# Power_Management_2FMC_RTM.net
KiCad netlist of a schematic drawn in Altium Designer
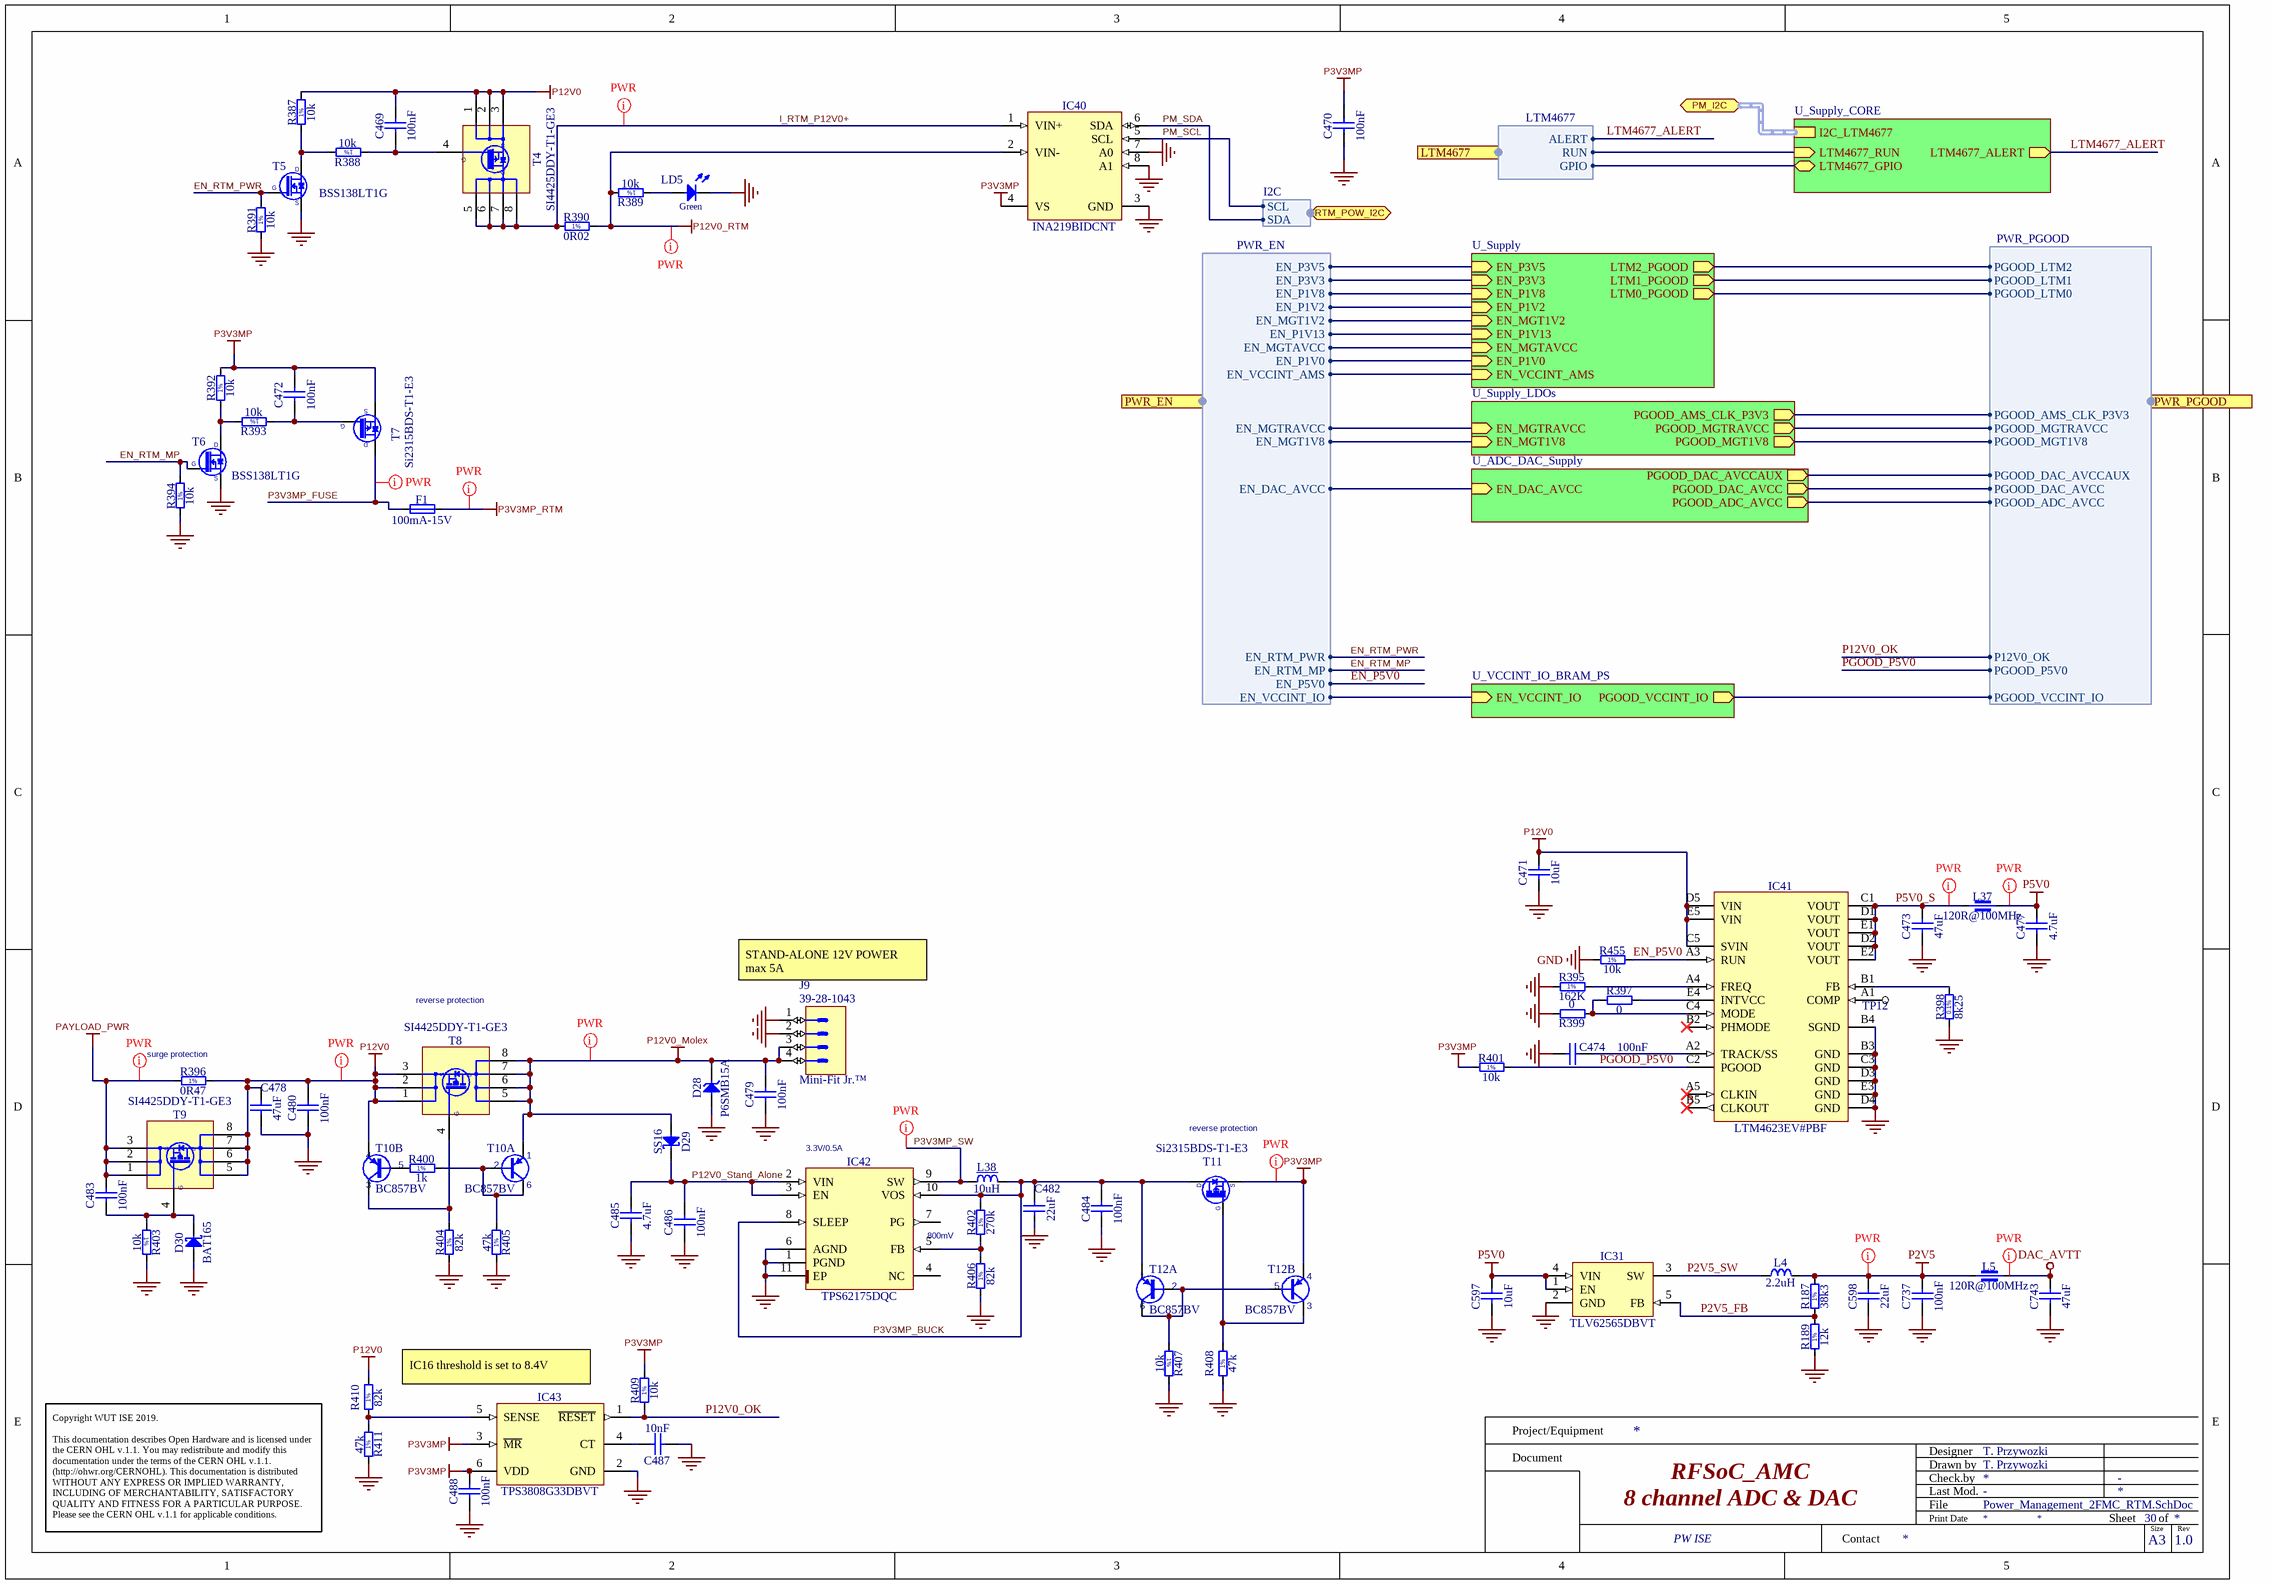
[diagram p0: Power_Management_2FMC_RTM.SchDoc]

(export (version "E")
  (design (tool "Eeschema 10.0.6"))
  (components
    (comp (ref "C469")
      (value "100nF")
      (footprint "CAPC1005X55N")
      (description "Non-polarised capacitor")
      (fields
        (field (name "MANUFACTURER PART NUMBER") "CC0402_100NF_16V_10%_X5R")
        (field (name "MANUFACTURER") "GENERIC")
        (field (name "AUTHOR") "CERN DEM JLC")
      )
      (libsource (lib "Capacitors") (part "Capacitor - non polarized"))
    )
    (comp (ref "C470")
      (value "100nF")
      (footprint "CAPC1005X55N")
      (description "Non-polarised capacitor")
      (fields
        (field (name "MANUFACTURER PART NUMBER") "CC0402_100NF_16V_10%_X5R")
        (field (name "MANUFACTURER") "GENERIC")
        (field (name "AUTHOR") "CERN DEM JLC")
      )
      (libsource (lib "Capacitors") (part "Capacitor - non polarized"))
    )
    (comp (ref "C471")
      (value "10uF")
      (footprint "CAPC2012X95N")
      (description "Non-polarised capacitor")
      (fields
        (field (name "PART NUMBER") "CC0805_10UF_25V_10%_X5R")
        (field (name "VOLTAGE") "25V")
        (field (name "AUTHOR") "CERN DEM JLC")
      )
      (libsource (lib "Capacitors") (part "Capacitor - non polarized"))
    )
    (comp (ref "C472")
      (value "100nF")
      (footprint "CAPC1005X55N")
      (description "Non-polarised capacitor")
      (fields
        (field (name "MANUFACTURER PART NUMBER") "CC0402_100NF_16V_10%_X5R")
        (field (name "MANUFACTURER") "GENERIC")
        (field (name "AUTHOR") "CERN DEM JLC")
      )
      (libsource (lib "Capacitors") (part "Capacitor - non polarized"))
    )
    (comp (ref "C473")
      (value "47uF")
      (footprint "CAPC2012X140N")
      (description "Non-polarised capacitor")
      (fields
        (field (name "MANUFACTURER PART NUMBER") "CC0805_47UF_6.3V_20%_X5R")
        (field (name "MANUFACTURER") "GENERIC")
        (field (name "AUTHOR") "CERN DEM JLC")
      )
      (libsource (lib "Capacitors") (part "Capacitor - non polarized"))
    )
    (comp (ref "C474")
      (value "100nF")
      (footprint "CAPC1005X55N")
      (description "Non-polarised capacitor")
      (fields
        (field (name "PART NUMBER") "CC0402_100NF_16V_10%_X5R")
        (field (name "VOLTAGE") "16V")
        (field (name "AUTHOR") "CERN DEM JLC")
      )
      (libsource (lib "Capacitors") (part "Capacitor - non polarized"))
    )
    (comp (ref "C477")
      (value "4.7uF")
      (footprint "CAPC1709X95N")
      (description "Non-polarised capacitor")
      (fields
        (field (name "MANUFACTURER PART NUMBER") "CC0603_4.7UF_16V_10%_X5R")
        (field (name "MANUFACTURER") "GENERIC")
        (field (name "AUTHOR") "CERN DEM JLC")
      )
      (libsource (lib "Capacitors") (part "Capacitor - non polarized"))
    )
    (comp (ref "C478")
      (value "47uF")
      (footprint "CAPC3216X180N")
      (description "Non-polarised capacitor")
      (fields
        (field (name "MANUFACTURER PART NUMBER") "CC1206_47UF_25V_20%_X5R")
        (field (name "MANUFACTURER") "GENERIC")
        (field (name "AUTHOR") "CERN DEM JLC")
      )
      (libsource (lib "Capacitors") (part "Capacitor - non polarized"))
    )
    (comp (ref "C479")
      (value "100nF")
      (footprint "CAPC1005X55N")
      (description "Non-polarised capacitor")
      (fields
        (field (name "MANUFACTURER PART NUMBER") "CC0402_100NF_16V_10%_X5R")
        (field (name "MANUFACTURER") "GENERIC")
        (field (name "AUTHOR") "CERN DEM JLC")
      )
      (libsource (lib "Capacitors") (part "Capacitor - non polarized"))
    )
    (comp (ref "C480")
      (value "100nF")
      (footprint "CAPC1005X55N")
      (description "Non-polarised capacitor")
      (fields
        (field (name "MANUFACTURER PART NUMBER") "CC0402_100NF_16V_10%_X5R")
        (field (name "MANUFACTURER") "GENERIC")
        (field (name "AUTHOR") "CERN DEM JLC")
      )
      (libsource (lib "Capacitors") (part "Capacitor - non polarized"))
    )
    (comp (ref "C482")
      (value "22uF")
      (footprint "CAPC2012X135N")
      (description "Non-polarised capacitor")
      (fields
        (field (name "MANUFACTURER PART NUMBER") "CC0805_22UF_16V_10%_X5R")
        (field (name "MANUFACTURER") "GENERIC")
        (field (name "AUTHOR") "CERN DEM JLC")
      )
      (libsource (lib "Capacitors") (part "Capacitor - non polarized"))
    )
    (comp (ref "C483")
      (value "100nF")
      (footprint "CAPC1005X55N")
      (description "Non-polarised capacitor")
      (fields
        (field (name "MANUFACTURER PART NUMBER") "CC0402_100NF_16V_10%_X5R")
        (field (name "MANUFACTURER") "GENERIC")
        (field (name "AUTHOR") "CERN DEM JLC")
      )
      (libsource (lib "Capacitors") (part "Capacitor - non polarized"))
    )
    (comp (ref "C484")
      (value "100nF")
      (footprint "CAPC1005X55N")
      (description "Non-polarised capacitor")
      (fields
        (field (name "MANUFACTURER PART NUMBER") "CC0402_100NF_16V_10%_X5R")
        (field (name "MANUFACTURER") "GENERIC")
        (field (name "AUTHOR") "CERN DEM JLC")
      )
      (libsource (lib "Capacitors") (part "Capacitor - non polarized"))
    )
    (comp (ref "C485")
      (value "4.7uF")
      (footprint "CAPC1709X95N")
      (description "Non-polarised capacitor")
      (fields
        (field (name "MANUFACTURER PART NUMBER") "CC0603_4.7UF_16V_10%_X5R")
        (field (name "MANUFACTURER") "GENERIC")
        (field (name "AUTHOR") "CERN DEM JLC")
      )
      (libsource (lib "Capacitors") (part "Capacitor - non polarized"))
    )
    (comp (ref "C486")
      (value "100nF")
      (footprint "CAPC1005X55N")
      (description "Non-polarised capacitor")
      (fields
        (field (name "MANUFACTURER PART NUMBER") "CC0402_100NF_16V_10%_X5R")
        (field (name "MANUFACTURER") "GENERIC")
        (field (name "AUTHOR") "CERN DEM JLC")
      )
      (libsource (lib "Capacitors") (part "Capacitor - non polarized"))
    )
    (comp (ref "C487")
      (value "10nF")
      (footprint "CAPC1005X55N")
      (description "Non-polarised capacitor")
      (fields
        (field (name "MANUFACTURER PART NUMBER") "CC0402_10NF_16V_10%_X7R")
        (field (name "MANUFACTURER") "GENERIC")
        (field (name "AUTHOR") "CERN DEM JLC")
      )
      (libsource (lib "Capacitors") (part "Capacitor - non polarized"))
    )
    (comp (ref "C488")
      (value "100nF")
      (footprint "CAPC1005X55N")
      (description "Non-polarised capacitor")
      (fields
        (field (name "MANUFACTURER PART NUMBER") "CC0402_100NF_16V_10%_X5R")
        (field (name "MANUFACTURER") "GENERIC")
        (field (name "AUTHOR") "CERN DEM JLC")
      )
      (libsource (lib "Capacitors") (part "Capacitor - non polarized"))
    )
    (comp (ref "C597")
      (value "10uF")
      (footprint "CAPC2012X95N")
      (description "Non-polarised capacitor")
      (fields
        (field (name "PART NUMBER") "CC0805_10UF_25V_10%_X5R")
        (field (name "VOLTAGE") "25V")
        (field (name "AUTHOR") "CERN DEM JLC")
      )
      (libsource (lib "Capacitors") (part "Capacitor - non polarized"))
    )
    (comp (ref "C598")
      (value "22uF")
      (footprint "CAPC1709X100N")
      (description "Non-polarised capacitor")
      (fields
        (field (name "PART NUMBER") "CC0603_22UF_6.3V_20%_X5R")
        (field (name "VOLTAGE") "6.3V")
        (field (name "AUTHOR") "CERN DEM JLC")
      )
      (libsource (lib "Capacitors") (part "Capacitor - non polarized"))
    )
    (comp (ref "C737")
      (value "100nF")
      (footprint "CAPC0603X33N")
      (description "Non-polarised capacitor")
      (fields
        (field (name "PART NUMBER") "CC0201_100NF_6.3V_10%_X5R")
        (field (name "VOLTAGE") "6.3V")
        (field (name "AUTHOR") "CERN DEM JLC")
      )
      (libsource (lib "Capacitors") (part "Capacitor - non polarized"))
    )
    (comp (ref "C743")
      (value "47uF")
      (footprint "CAPC2012X140N")
      (description "Non-polarised capacitor")
      (fields
        (field (name "MANUFACTURER PART NUMBER") "CC0805_47UF_6.3V_20%_X5R")
        (field (name "MANUFACTURER") "GENERIC")
        (field (name "AUTHOR") "CERN DEM JLC")
      )
      (libsource (lib "Capacitors") (part "Capacitor - non polarized"))
    )
    (comp (ref "D28")
      (value "P6SMB15A")
      (footprint "DIOM5436X261N")
      (description "Transient Voltage Suppressor Diode (Uni-Directional)")
      (fields
        (field (name "MANUFACTURER") "LITTELFUSE")
        (field (name "VOLTAGE") "15V")
        (field (name "AUTHOR") "CERN DEM JLC")
      )
      (libsource (lib "ICs And Semiconductors") (part "Diode TVS Uni-Directional"))
    )
    (comp (ref "D29")
      (value "SS16")
      (footprint "DIOM5127X229N")
      (description "Schottky Diode")
      (fields
        (field (name "MANUFACTURER") "VISHAY GENERAL SEMICONDUCTOR")
        (field (name "VOLTAGE") "60V")
        (field (name "AUTHOR") "CERN DEM JLC")
      )
      (libsource (lib "ICs And Semiconductors") (part "Diode Schottky"))
    )
    (comp (ref "D30")
      (value "BAT165")
      (footprint "SOD2512X110N")
      (description "Schottky Diode")
      (fields
        (field (name "MANUFACTURER") "INFINEON")
        (field (name "VOLTAGE") "40V")
        (field (name "AUTHOR") "CERN DEM JLC")
      )
      (libsource (lib "ICs And Semiconductors") (part "Diode Schottky"))
    )
    (comp (ref "F1")
      (value "100mA-15V")
      (footprint "FUSR_LITTELFUSE_0805L010")
      (description "Fuse")
      (fields
        (field (name "MANUFACTURER PART NUMBER") "0805L010YR")
        (field (name "MANUFACTURER") "LITTELFUSE")
        (field (name "AUTHOR") "CERN DEM JLC")
      )
      (libsource (lib "Eletro-mechanical") (part "Fuse"))
    )
    (comp (ref "IC31")
      (value "TLV62565DBVT")
      (footprint "SOT95P280X145-5N")
      (description "1.5A High Efficiency Step-Down Converter, Adjustable Output Voltage")
      (fields (field (name "MANUFACTURER") "TEXAS INSTRUMENTS") (field (name "AUTHOR") "CERN DEM JMW"))
      (libsource (lib "ICs And Semiconductors") (part "TLV62565"))
    )
    (comp (ref "IC40")
      (value "INA219BIDCNT")
      (footprint "SOT65P280X145-8N")
      (description "Zero-Drift, Bi-Directional CURRENT/POWER MONITOR with I2C™ Interface")
      (fields (field (name "MANUFACTURER") "TEXAS INSTRUMENTS") (field (name "AUTHOR") "CERN DEM JLC"))
      (libsource (lib "ICs And Semiconductors") (part "INA219BIDCNT"))
    )
    (comp (ref "IC41")
      (value "LTM4623EV#PBF")
      (footprint "LGA25C127P5X5_625X625X192")
      (description "4V-20V to 0.6V-5.5V, Iout 3A Step-Down DC/DC uModule Regulator")
      (fields (field (name "MANUFACTURER") "LINEAR TECHNOLOGY") (field (name "AUTHOR") "CERN DEM JMW"))
      (libsource (lib "ICs And Semiconductors") (part "LTM4623"))
    )
    (comp (ref "IC42")
      (value "TPS62175DQC")
      (footprint "SON50P200X300X80-11N-R94X250")
      (description "4.75-28VDC to 1-6VDC, 500mA Step-Down Converter With Sleep Mode")
      (fields (field (name "MANUFACTURER") "TEXAS INSTRUMENTS") (field (name "AUTHOR") "CERN DEM JMW"))
      (libsource (lib "ICs And Semiconductors") (part "TPS62175"))
    )
    (comp (ref "IC43")
      (value "TPS3808G33DBVT")
      (footprint "SOT95P280X145-6N")
      (description "Low Quiescent Current, Programmable-Delay Supervisory Circuit")
      (fields (field (name "MANUFACTURER") "TEXAS INSTRUMENTS") (field (name "AUTHOR") "CERN DEM JLC"))
      (libsource (lib "ICs And Semiconductors") (part "TPS3808xxxDBV"))
    )
    (comp (ref "J9")
      (value "Mini-Fit Jr.™")
      (footprint "MOLEX_39-28-1043")
      (description "Connector 4 Male")
      (fields
        (field (name "MANUFACTURER PART NUMBER") "39-28-1043")
        (field (name "MANUFACTURER") "MOLEX")
        (field (name "PART NUMBER") "MOLEX_39-28-1043")
        (field (name "AUTHOR") "CERN DEM JLC")
      )
      (libsource (lib "Connectors") (part "Connector 4 Male"))
    )
    (comp (ref "L4")
      (value "2.2uH")
      (footprint "IND_WURTH_WE-PMCI_0806LR")
      (description "Inductor")
      (fields
        (field (name "PART NUMBER") "IND_2.2UH_20%_WURTH_WE-PMCI_74479276222C")
        (field (name "POWER") "1.1A")
        (field (name "AUTHOR") "CERN DEM JLC")
      )
      (libsource (lib "Inductors & Transformers") (part "Inductor"))
    )
    (comp (ref "L5")
      (value "120R@100MHz")
      (footprint "INDC1608X95N")
      (fields
        (field (name "MANUFACTURER PART NUMBER") "BLM18PG121SN1D")
        (field (name "MANUFACTURER") "MURATA")
        (field (name "PART NUMBER") "IND0603_MURATA_BLM18PG121SN1D")
        (field (name "AUTHOR") "CERN DEM BC")
      )
      (libsource (lib "Inductors & Transformers") (part "Ferrite Bead"))
    )
    (comp (ref "L37")
      (value "120R@100MHz")
      (footprint "INDC1608X95N")
      (fields
        (field (name "MANUFACTURER PART NUMBER") "BLM18PG121SN1D")
        (field (name "MANUFACTURER") "MURATA")
        (field (name "PART NUMBER") "IND0603_MURATA_BLM18PG121SN1D")
        (field (name "AUTHOR") "CERN DEM BC")
      )
      (libsource (lib "Inductors & Transformers") (part "Ferrite Bead"))
    )
    (comp (ref "L38")
      (value "10uH")
      (footprint "IND_MURATA-PS_8400")
      (description "Inductor With Core")
      (fields
        (field (name "MANUFACTURER PART NUMBER") "84103C")
        (field (name "MANUFACTURER") "MURATA POWER SOLUTIONS")
        (field (name "AUTHOR") "CERN DEM JLC")
      )
      (libsource (lib "Inductors & Transformers") (part "Inductor With Magnetic core"))
    )
    (comp (ref "LD5")
      (value "Green")
      (footprint "LED_KINGBRIGHT_KPH-1608CGCK")
      (description "LED Green 1C 2A")
      (fields
        (field (name "MANUFACTURER PART NUMBER") "KPH-1608CGCK")
        (field (name "MANUFACTURER") "KINGBRIGHT")
        (field (name "AUTHOR") "CERN DEM JLC")
      )
      (libsource (lib "ICs And Semiconductors") (part "LED Green 1C 2A"))
    )
    (comp (ref "R187")
      (value "38k3")
      (footprint "RESC1005X40N")
      (description "Resistor - 1%")
      (fields
        (field (name "PART NUMBER") "R0402_38K3_1%_0.0625W_100PPM")
        (field (name "POWER") "0.0625W")
        (field (name "AUTHOR") "CERN DEM BC")
      )
      (libsource (lib "Resistors") (part "Resistor - 1%"))
    )
    (comp (ref "R189")
      (value "12k")
      (footprint "RESC1005X40N")
      (description "Resistor - 1%")
      (fields
        (field (name "PART NUMBER") "R0402_12K_1%_0.0625W_100PPM")
        (field (name "POWER") "0.0625W")
        (field (name "AUTHOR") "CERN DEM JLC")
      )
      (libsource (lib "Resistors") (part "Resistor - 1%"))
    )
    (comp (ref "R387")
      (value "10k")
      (footprint "RESC1005X40N")
      (description "Resistor - 1%")
      (fields
        (field (name "MANUFACTURER PART NUMBER") "R0402_10K_1%_0.0625W_100PPM")
        (field (name "MANUFACTURER") "GENERIC")
        (field (name "AUTHOR") "CERN DEM JLC")
      )
      (libsource (lib "Resistors") (part "Resistor - 1%"))
    )
    (comp (ref "R388")
      (value "10k")
      (footprint "RESC1005X40N")
      (description "Resistor - 1%")
      (fields
        (field (name "MANUFACTURER PART NUMBER") "R0402_10K_1%_0.0625W_100PPM")
        (field (name "MANUFACTURER") "GENERIC")
        (field (name "AUTHOR") "CERN DEM JLC")
      )
      (libsource (lib "Resistors") (part "Resistor - 1%"))
    )
    (comp (ref "R389")
      (value "10k")
      (footprint "RESC1005X40N")
      (description "Resistor - 1%")
      (fields
        (field (name "MANUFACTURER PART NUMBER") "R0402_10K_1%_0.0625W_100PPM")
        (field (name "MANUFACTURER") "GENERIC")
        (field (name "AUTHOR") "CERN DEM JLC")
      )
      (libsource (lib "Resistors") (part "Resistor - 1%"))
    )
    (comp (ref "R390")
      (value "0R02")
      (footprint "RESC_VISHAY_WSL2512_0R007-0R5")
      (description "Resistor - 1%")
      (fields
        (field (name "MANUFACTURER PART NUMBER") "WSL2512R0200FEA")
        (field (name "MANUFACTURER") "VISHAY DALE")
        (field (name "AUTHOR") "CERN DEM JLC")
      )
      (libsource (lib "Resistors") (part "Resistor - 1%"))
    )
    (comp (ref "R391")
      (value "10k")
      (footprint "RESC1005X40N")
      (description "Resistor - 1%")
      (fields
        (field (name "MANUFACTURER PART NUMBER") "R0402_10K_1%_0.0625W_100PPM")
        (field (name "MANUFACTURER") "GENERIC")
        (field (name "AUTHOR") "CERN DEM JLC")
      )
      (libsource (lib "Resistors") (part "Resistor - 1%"))
    )
    (comp (ref "R392")
      (value "10k")
      (footprint "RESC1005X40N")
      (description "Resistor - 1%")
      (fields
        (field (name "MANUFACTURER PART NUMBER") "R0402_10K_1%_0.0625W_100PPM")
        (field (name "MANUFACTURER") "GENERIC")
        (field (name "AUTHOR") "CERN DEM JLC")
      )
      (libsource (lib "Resistors") (part "Resistor - 1%"))
    )
    (comp (ref "R393")
      (value "10k")
      (footprint "RESC1005X40N")
      (description "Resistor - 1%")
      (fields
        (field (name "MANUFACTURER PART NUMBER") "R0402_10K_1%_0.0625W_100PPM")
        (field (name "MANUFACTURER") "GENERIC")
        (field (name "AUTHOR") "CERN DEM JLC")
      )
      (libsource (lib "Resistors") (part "Resistor - 1%"))
    )
    (comp (ref "R394")
      (value "10k")
      (footprint "RESC1005X40N")
      (description "Resistor - 1%")
      (fields
        (field (name "MANUFACTURER PART NUMBER") "R0402_10K_1%_0.0625W_100PPM")
        (field (name "MANUFACTURER") "GENERIC")
        (field (name "AUTHOR") "CERN DEM JLC")
      )
      (libsource (lib "Resistors") (part "Resistor - 1%"))
    )
    (comp (ref "R395")
      (value "162K")
      (footprint "RESC1608X55N")
      (description "Resistor - 1%")
      (fields
        (field (name "PART NUMBER") "R0603_162K_1%_0.1W_100PPM")
        (field (name "POWER") "0.1W")
        (field (name "AUTHOR") "CERN DEM BC")
      )
      (libsource (lib "Resistors") (part "Resistor - 1%"))
    )
    (comp (ref "R396")
      (value "0R47")
      (footprint "RESC3216X65N")
      (description "Resistor - 1%")
      (fields
        (field (name "MANUFACTURER PART NUMBER") "RL1206FR-7W0R47  (35051914707)")
        (field (name "MANUFACTURER") "YAGEO PHYCOMP")
        (field (name "AUTHOR") "CERN DEM JLC")
      )
      (libsource (lib "Resistors") (part "Resistor - 1%"))
    )
    (comp (ref "R397")
      (value "0")
      (footprint "RESC1005X40N")
      (description "Resistor")
      (fields
        (field (name "MANUFACTURER PART NUMBER") "R0402_0R_JUMPER")
        (field (name "MANUFACTURER") "GENERIC")
        (field (name "AUTHOR") "CERN DEM JLC")
      )
      (libsource (lib "Resistors") (part "Resistor"))
    )
    (comp (ref "R398")
      (value "8k25")
      (footprint "RESC1608X55N")
      (description "Resistor - 0.1%")
      (fields
        (field (name "PART NUMBER") "R0603_8K25_0.1%_0.063W_10PPM")
        (field (name "POWER") "0.063W")
        (field (name "AUTHOR") "CERN DEM JLC")
      )
      (libsource (lib "Resistors") (part "Resistor - 0.1%"))
    )
    (comp (ref "R399")
      (value "0")
      (footprint "RESC1005X40N")
      (description "Resistor")
      (fields
        (field (name "MANUFACTURER PART NUMBER") "R0402_0R_JUMPER")
        (field (name "MANUFACTURER") "GENERIC")
        (field (name "AUTHOR") "CERN DEM JLC")
      )
      (libsource (lib "Resistors") (part "Resistor"))
    )
    (comp (ref "R400")
      (value "1k")
      (footprint "RESC1005X40N")
      (description "Resistor - 1%")
      (fields
        (field (name "MANUFACTURER PART NUMBER") "R0402_1K_1%_0.0625W_100PPM")
        (field (name "MANUFACTURER") "GENERIC")
        (field (name "AUTHOR") "CERN DEM JLC")
      )
      (libsource (lib "Resistors") (part "Resistor - 1%"))
    )
    (comp (ref "R401")
      (value "10k")
      (footprint "RESC1005X40N")
      (description "Resistor - 1%")
      (fields
        (field (name "MANUFACTURER PART NUMBER") "R0402_10K_1%_0.0625W_100PPM")
        (field (name "MANUFACTURER") "GENERIC")
        (field (name "AUTHOR") "CERN DEM JLC")
      )
      (libsource (lib "Resistors") (part "Resistor - 1%"))
    )
    (comp (ref "R402")
      (value "270k")
      (footprint "RESC1005X40N")
      (description "Resistor - 1%")
      (fields
        (field (name "MANUFACTURER PART NUMBER") "R0402_270K_1%_0.0625W_100PPM")
        (field (name "MANUFACTURER") "GENERIC")
        (field (name "AUTHOR") "CERN DEM JLC")
      )
      (libsource (lib "Resistors") (part "Resistor - 1%"))
    )
    (comp (ref "R403")
      (value "10k")
      (footprint "RESC1005X40N")
      (description "Resistor - 1%")
      (fields
        (field (name "MANUFACTURER PART NUMBER") "R0402_10K_1%_0.0625W_100PPM")
        (field (name "MANUFACTURER") "GENERIC")
        (field (name "AUTHOR") "CERN DEM JLC")
      )
      (libsource (lib "Resistors") (part "Resistor - 1%"))
    )
    (comp (ref "R404")
      (value "82k")
      (footprint "RESC1005X40N")
      (description "Resistor - 1%")
      (fields
        (field (name "MANUFACTURER PART NUMBER") "R0402_82K_1%_0.0625W_100PPM")
        (field (name "MANUFACTURER") "GENERIC")
        (field (name "AUTHOR") "CERN DEM JLC")
      )
      (libsource (lib "Resistors") (part "Resistor - 1%"))
    )
    (comp (ref "R405")
      (value "47k")
      (footprint "RESC1005X40N")
      (description "Resistor - 1%")
      (fields
        (field (name "MANUFACTURER PART NUMBER") "R0402_47K_1%_0.0625W_100PPM")
        (field (name "MANUFACTURER") "GENERIC")
        (field (name "AUTHOR") "CERN DEM JLC")
      )
      (libsource (lib "Resistors") (part "Resistor - 1%"))
    )
    (comp (ref "R406")
      (value "82k")
      (footprint "RESC1005X40N")
      (description "Resistor - 1%")
      (fields
        (field (name "MANUFACTURER PART NUMBER") "R0402_82K_1%_0.0625W_100PPM")
        (field (name "MANUFACTURER") "GENERIC")
        (field (name "AUTHOR") "CERN DEM JLC")
      )
      (libsource (lib "Resistors") (part "Resistor - 1%"))
    )
    (comp (ref "R407")
      (value "10k")
      (footprint "RESC1005X40N")
      (description "Resistor - 1%")
      (fields
        (field (name "MANUFACTURER PART NUMBER") "R0402_10K_1%_0.0625W_100PPM")
        (field (name "MANUFACTURER") "GENERIC")
        (field (name "AUTHOR") "CERN DEM JLC")
      )
      (libsource (lib "Resistors") (part "Resistor - 1%"))
    )
    (comp (ref "R408")
      (value "47k")
      (footprint "RESC1005X40N")
      (description "Resistor - 1%")
      (fields
        (field (name "MANUFACTURER PART NUMBER") "R0402_47K_1%_0.0625W_100PPM")
        (field (name "MANUFACTURER") "GENERIC")
        (field (name "AUTHOR") "CERN DEM JLC")
      )
      (libsource (lib "Resistors") (part "Resistor - 1%"))
    )
    (comp (ref "R409")
      (value "10k")
      (footprint "RESC1005X40N")
      (description "Resistor - 1%")
      (fields
        (field (name "MANUFACTURER PART NUMBER") "R0402_10K_1%_0.0625W_100PPM")
        (field (name "MANUFACTURER") "GENERIC")
        (field (name "AUTHOR") "CERN DEM JLC")
      )
      (libsource (lib "Resistors") (part "Resistor - 1%"))
    )
    (comp (ref "R410")
      (value "82k")
      (footprint "RESC1005X40N")
      (description "Resistor - 1%")
      (fields
        (field (name "MANUFACTURER PART NUMBER") "R0402_82K_1%_0.0625W_100PPM")
        (field (name "MANUFACTURER") "GENERIC")
        (field (name "AUTHOR") "CERN DEM JLC")
      )
      (libsource (lib "Resistors") (part "Resistor - 1%"))
    )
    (comp (ref "R411")
      (value "47k")
      (footprint "RESC1005X40N")
      (description "Resistor - 1%")
      (fields
        (field (name "MANUFACTURER PART NUMBER") "R0402_47K_1%_0.0625W_100PPM")
        (field (name "MANUFACTURER") "GENERIC")
        (field (name "AUTHOR") "CERN DEM JLC")
      )
      (libsource (lib "Resistors") (part "Resistor - 1%"))
    )
    (comp (ref "R455")
      (value "10k")
      (footprint "RESC1005X40N")
      (description "Resistor - 1%")
      (fields
        (field (name "MANUFACTURER PART NUMBER") "R0402_10K_1%_0.0625W_100PPM")
        (field (name "MANUFACTURER") "GENERIC")
        (field (name "AUTHOR") "CERN DEM JLC")
      )
      (libsource (lib "Resistors") (part "Resistor - 1%"))
    )
    (comp (ref "T4")
      (value "SI4425DDY-T1-GE3")
      (footprint "SOIC127P600X175-8N")
      (description "-30V -19.7A P-Channel MOSFET")
      (fields (field (name "MANUFACTURER") "VISHAY SILICONIX") (field (name "AUTHOR") "CERN DEM MR"))
      (libsource (lib "") (part "SI4425DDY_1"))
    )
    (comp (ref "T5")
      (value "BSS138LT1G")
      (footprint "SOT95P240X110-3N")
      (description "N-CHANNEL MOSFET WITH DIODE")
      (fields (field (name "MANUFACTURER") "ON SEMICONDUCTOR") (field (name "AUTHOR") "CERN DEM JLC"))
      (libsource (lib "ICs And Semiconductors") (part "N-MOSFET-D 1G 2S 3D"))
    )
    (comp (ref "T6")
      (value "BSS138LT1G")
      (footprint "SOT95P240X110-3N")
      (description "N-CHANNEL MOSFET WITH DIODE")
      (fields (field (name "MANUFACTURER") "ON SEMICONDUCTOR") (field (name "AUTHOR") "CERN DEM JLC"))
      (libsource (lib "ICs And Semiconductors") (part "N-MOSFET-D 1G 2S 3D"))
    )
    (comp (ref "T7")
      (value "Si2315BDS-T1-E3")
      (footprint "SOT95P237X112-3N")
      (description "P-CHANNEL MOSFET WITH DIODE")
      (fields (field (name "MANUFACTURER") "VISHAY SILICONIX") (field (name "AUTHOR") "CERN DEM JLC"))
      (libsource (lib "ICs And Semiconductors") (part "P-MOSFET-D 1G 2S 3D"))
    )
    (comp (ref "T8")
      (value "SI4425DDY-T1-GE3")
      (footprint "SOIC127P600X175-8N")
      (description "-30V -19.7A P-Channel MOSFET")
      (fields (field (name "MANUFACTURER") "VISHAY SILICONIX") (field (name "AUTHOR") "CERN DEM MR"))
      (libsource (lib "ICs And Semiconductors") (part "SI4425DDY"))
    )
    (comp (ref "T9")
      (value "SI4425DDY-T1-GE3")
      (footprint "SOIC127P600X175-8N")
      (description "-30V -19.7A P-Channel MOSFET")
      (fields (field (name "MANUFACTURER") "VISHAY SILICONIX") (field (name "AUTHOR") "CERN DEM MR"))
      (libsource (lib "ICs And Semiconductors") (part "SI4425DDY"))
    )
    (comp (ref "T10")
      (value "BC857BV")
      (footprint "SOTFL50P160X60-6N")
      (description "45V, 100mA PNP General Purpose Double Transistor")
      (fields (field (name "MANUFACTURER") "NXP SEMICONDUCTORS") (field (name "AUTHOR") "CERN DEM JLC"))
      (libsource (lib "") (part "BC857BV_1"))
    )
    (comp (ref "T11")
      (value "Si2315BDS-T1-E3")
      (footprint "SOT95P237X112-3N")
      (description "P-CHANNEL MOSFET WITH DIODE")
      (fields (field (name "MANUFACTURER") "VISHAY SILICONIX") (field (name "AUTHOR") "CERN DEM JLC"))
      (libsource (lib "ICs And Semiconductors") (part "P-MOSFET-D 1G 2S 3D"))
    )
    (comp (ref "T12")
      (value "BC857BV")
      (footprint "SOTFL50P160X60-6N")
      (description "45V, 100mA PNP General Purpose Double Transistor")
      (fields (field (name "MANUFACTURER") "NXP SEMICONDUCTORS") (field (name "AUTHOR") "CERN DEM JLC"))
      (libsource (lib "") (part "BC857BV_2"))
    )
    (comp (ref "TP12")
      (value "TP")
      (footprint "TP")
      (description "Testpoint")
      (libsource (lib "LIBRARY_SCH") (part "TP"))
    )
  )
  (nets
    (net (code "17") (name "/EN_P5V0") (class "Default")
      (node (ref "IC41") (pin "A3") (pinfunction "RUN_A3") (pintype "input"))
      (node (ref "R455") (pin "2") (pinfunction "2_2") (pintype "passive"))
    )
    (net (code "18") (name "/EN_RTM_MP") (class "Default")
      (node (ref "R394") (pin "2") (pinfunction "2_2") (pintype "passive"))
      (node (ref "T6") (pin "1") (pinfunction "G_1") (pintype "passive"))
    )
    (net (code "19") (name "/EN_RTM_PWR") (class "Default")
      (node (ref "R391") (pin "2") (pinfunction "2_2") (pintype "passive"))
      (node (ref "T5") (pin "1") (pinfunction "G_1") (pintype "passive"))
    )
    (net (code "22") (name "/I_RTM_P12V0+") (class "Default")
      (node (ref "IC40") (pin "1") (pinfunction "VIN+_1") (pintype "input"))
      (node (ref "R390") (pin "1") (pinfunction "1_1") (pintype "passive"))
      (node (ref "T4") (pin "5") (pinfunction "D_5") (pintype "passive"))
      (node (ref "T4") (pin "6") (pinfunction "D_6") (pintype "passive"))
      (node (ref "T4") (pin "7") (pinfunction "D_7") (pintype "passive"))
      (node (ref "T4") (pin "8") (pinfunction "D_8") (pintype "passive"))
    )
    (net (code "29") (name "/P2V5_FB") (class "Default")
      (node (ref "IC31") (pin "5") (pinfunction "FB_5") (pintype "input"))
      (node (ref "R187") (pin "1") (pinfunction "1_1") (pintype "passive"))
      (node (ref "R189") (pin "2") (pinfunction "2_2") (pintype "passive"))
    )
    (net (code "30") (name "/P2V5_SW") (class "Default")
      (node (ref "IC31") (pin "3") (pinfunction "SW_3") (pintype "power_in"))
      (node (ref "L4") (pin "1") (pinfunction "1_1") (pintype "passive"))
    )
    (net (code "31") (name "/P3V3MP_BUCK") (class "Default")
      (node (ref "C482") (pin "2") (pinfunction "2_2") (pintype "passive"))
      (node (ref "C484") (pin "2") (pinfunction "2_2") (pintype "passive"))
      (node (ref "IC42") (pin "10") (pinfunction "VOS_10") (pintype "input"))
      (node (ref "IC42") (pin "8") (pinfunction "SLEEP_8") (pintype "input"))
      (node (ref "L38") (pin "2") (pinfunction "2_2") (pintype "passive"))
      (node (ref "R402") (pin "2") (pinfunction "2_2") (pintype "passive"))
      (node (ref "T11") (pin "3") (pinfunction "D_3") (pintype "passive"))
      (node (ref "T12") (pin "1") (pinfunction "E_1") (pintype "passive"))
    )
    (net (code "32") (name "/P3V3MP_FUSE") (class "Default")
      (node (ref "F1") (pin "1") (pinfunction "1_1") (pintype "passive"))
      (node (ref "T7") (pin "3") (pinfunction "D_3") (pintype "passive"))
    )
    (net (code "33") (name "/P3V3MP_SW") (class "Default")
      (node (ref "IC42") (pin "9") (pinfunction "SW_9") (pintype "output"))
      (node (ref "L38") (pin "1") (pinfunction "1_1") (pintype "passive"))
    )
    (net (code "34") (name "/P5V0_S") (class "Default")
      (node (ref "C473") (pin "2") (pinfunction "2_2") (pintype "passive"))
      (node (ref "IC41") (pin "C1") (pinfunction "VOUT_C1") (pintype "power_in"))
      (node (ref "IC41") (pin "D1") (pinfunction "VOUT_D1") (pintype "power_in"))
      (node (ref "IC41") (pin "D2") (pinfunction "VOUT_D2") (pintype "power_in"))
      (node (ref "IC41") (pin "E1") (pinfunction "VOUT_E1") (pintype "power_in"))
      (node (ref "IC41") (pin "E2") (pinfunction "VOUT_E2") (pintype "power_in"))
      (node (ref "L37") (pin "1") (pinfunction "1_1") (pintype "passive"))
    )
    (net (code "35") (name "/P12V0_OK") (class "Default")
      (node (ref "IC43") (pin "1") (pinfunction "~{RESET}_1") (pintype "output"))
      (node (ref "R409") (pin "1") (pinfunction "1_1") (pintype "passive"))
    )
    (net (code "36") (name "/P12V0_Stand_Alone") (class "Default")
      (node (ref "C485") (pin "2") (pinfunction "2_2") (pintype "passive"))
      (node (ref "C486") (pin "2") (pinfunction "2_2") (pintype "passive"))
      (node (ref "D29") (pin "1") (pinfunction "C_1") (pintype "passive"))
      (node (ref "IC42") (pin "2") (pinfunction "VIN_2") (pintype "input"))
      (node (ref "IC42") (pin "3") (pinfunction "EN_3") (pintype "input"))
    )
    (net (code "43") (name "/PGOOD_P5V0") (class "Default")
      (node (ref "IC41") (pin "C2") (pinfunction "PGOOD_C2") (pintype "open_collector"))
      (node (ref "R401") (pin "2") (pinfunction "2_2") (pintype "passive"))
    )
    (net (code "46") (name "/PM_SCL") (class "Default")
      (node (ref "IC40") (pin "5") (pinfunction "SCL_5") (pintype "input"))
    )
    (net (code "47") (name "/PM_SDA") (class "Default")
      (node (ref "IC40") (pin "6") (pinfunction "SDA_6") (pintype "bidirectional"))
    )
    (net (code "52") (name "DAC_AVTT") (class "Default")
      (node (ref "C743") (pin "2") (pinfunction "2_2") (pintype "passive"))
      (node (ref "L5") (pin "2") (pinfunction "2_2") (pintype "passive"))
    )
    (net (code "53") (name "GND") (class "Default")
      (node (ref "C470") (pin "1") (pinfunction "1_1") (pintype "passive"))
      (node (ref "C471") (pin "1") (pinfunction "1_1") (pintype "passive"))
      (node (ref "C473") (pin "1") (pinfunction "1_1") (pintype "passive"))
      (node (ref "C474") (pin "2") (pinfunction "2_2") (pintype "passive"))
      (node (ref "C477") (pin "1") (pinfunction "1_1") (pintype "passive"))
      (node (ref "C478") (pin "1") (pinfunction "1_1") (pintype "passive"))
      (node (ref "C479") (pin "1") (pinfunction "1_1") (pintype "passive"))
      (node (ref "C480") (pin "1") (pinfunction "1_1") (pintype "passive"))
      (node (ref "C482") (pin "1") (pinfunction "1_1") (pintype "passive"))
      (node (ref "C484") (pin "1") (pinfunction "1_1") (pintype "passive"))
      (node (ref "C485") (pin "1") (pinfunction "1_1") (pintype "passive"))
      (node (ref "C486") (pin "1") (pinfunction "1_1") (pintype "passive"))
      (node (ref "C487") (pin "1") (pinfunction "1_1") (pintype "passive"))
      (node (ref "C488") (pin "1") (pinfunction "1_1") (pintype "passive"))
      (node (ref "C597") (pin "1") (pinfunction "1_1") (pintype "passive"))
      (node (ref "C598") (pin "1") (pinfunction "1_1") (pintype "passive"))
      (node (ref "C737") (pin "1") (pinfunction "1_1") (pintype "passive"))
      (node (ref "C743") (pin "1") (pinfunction "1_1") (pintype "passive"))
      (node (ref "D28") (pin "2") (pinfunction "A_2") (pintype "passive"))
      (node (ref "D30") (pin "2") (pinfunction "A_2") (pintype "passive"))
      (node (ref "IC31") (pin "2") (pinfunction "GND_2") (pintype "power_in"))
      (node (ref "IC40") (pin "3") (pinfunction "GND_3") (pintype "power_in"))
      (node (ref "IC40") (pin "7") (pinfunction "A0_7") (pintype "input"))
      (node (ref "IC40") (pin "8") (pinfunction "A1_8") (pintype "input"))
      (node (ref "IC41") (pin "B3") (pinfunction "GND_B3") (pintype "power_in"))
      (node (ref "IC41") (pin "B4") (pinfunction "SGND_B4") (pintype "power_in"))
      (node (ref "IC41") (pin "C3") (pinfunction "GND_C3") (pintype "power_in"))
      (node (ref "IC41") (pin "D3") (pinfunction "GND_D3") (pintype "power_in"))
      (node (ref "IC41") (pin "D4") (pinfunction "GND_D4") (pintype "power_in"))
      (node (ref "IC41") (pin "E3") (pinfunction "GND_E3") (pintype "power_in"))
      (node (ref "IC42") (pin "1") (pinfunction "PGND_1") (pintype "power_in"))
      (node (ref "IC42") (pin "11") (pinfunction "EP_11") (pintype "power_in"))
      (node (ref "IC42") (pin "6") (pinfunction "AGND_6") (pintype "power_in"))
      (node (ref "IC43") (pin "2") (pinfunction "GND_2") (pintype "power_in"))
      (node (ref "J9") (pin "1") (pinfunction "1_1") (pintype "bidirectional"))
      (node (ref "J9") (pin "2") (pinfunction "2_2") (pintype "bidirectional"))
      (node (ref "LD5") (pin "1") (pinfunction "C_1") (pintype "passive"))
      (node (ref "R189") (pin "1") (pinfunction "1_1") (pintype "passive"))
      (node (ref "R391") (pin "1") (pinfunction "1_1") (pintype "passive"))
      (node (ref "R394") (pin "1") (pinfunction "1_1") (pintype "passive"))
      (node (ref "R395") (pin "1") (pinfunction "1_1") (pintype "passive"))
      (node (ref "R398") (pin "1") (pinfunction "1_1") (pintype "passive"))
      (node (ref "R399") (pin "2") (pinfunction "2_2") (pintype "passive"))
      (node (ref "R403") (pin "2") (pinfunction "2_2") (pintype "passive"))
      (node (ref "R404") (pin "1") (pinfunction "1_1") (pintype "passive"))
      (node (ref "R405") (pin "1") (pinfunction "1_1") (pintype "passive"))
      (node (ref "R406") (pin "1") (pinfunction "1_1") (pintype "passive"))
      (node (ref "R407") (pin "2") (pinfunction "2_2") (pintype "passive"))
      (node (ref "R408") (pin "1") (pinfunction "1_1") (pintype "passive"))
      (node (ref "R411") (pin "1") (pinfunction "1_1") (pintype "passive"))
      (node (ref "R455") (pin "1") (pinfunction "1_1") (pintype "passive"))
      (node (ref "T5") (pin "2") (pinfunction "S_2") (pintype "passive"))
      (node (ref "T6") (pin "2") (pinfunction "S_2") (pintype "passive"))
    )
    (net (code "54") (name "Net-(C469-Pad1)") (class "Default")
      (node (ref "C469") (pin "1") (pinfunction "1_1") (pintype "passive"))
      (node (ref "R388") (pin "1") (pinfunction "1_1") (pintype "passive"))
      (node (ref "T4") (pin "4") (pinfunction "S_4") (pintype "passive"))
    )
    (net (code "55") (name "Net-(D30-C)") (class "Default")
      (node (ref "C483") (pin "1") (pinfunction "1_1") (pintype "passive"))
      (node (ref "D30") (pin "1") (pinfunction "C_1") (pintype "passive"))
      (node (ref "R403") (pin "1") (pinfunction "1_1") (pintype "passive"))
      (node (ref "T9") (pin "4") (pinfunction "S_4") (pintype "passive"))
    )
    (net (code "56") (name "Net-(IC41-COMP)") (class "Default")
      (node (ref "IC41") (pin "A1") (pinfunction "COMP_A1") (pintype "input"))
      (node (ref "TP12") (pin "1") (pintype "passive"))
    )
    (net (code "57") (name "Net-(IC41-FB)") (class "Default")
      (node (ref "IC41") (pin "B1") (pinfunction "FB_B1") (pintype "input"))
      (node (ref "R398") (pin "2") (pinfunction "2_2") (pintype "passive"))
    )
    (net (code "58") (name "Net-(IC41-FREQ)") (class "Default")
      (node (ref "IC41") (pin "A4") (pinfunction "FREQ_A4") (pintype "input"))
      (node (ref "R395") (pin "2") (pinfunction "2_2") (pintype "passive"))
    )
    (net (code "59") (name "Net-(IC41-INTVCC)") (class "Default")
      (node (ref "IC41") (pin "E4") (pinfunction "INTVCC_E4") (pintype "power_in"))
      (node (ref "R397") (pin "2") (pinfunction "2_2") (pintype "passive"))
    )
    (net (code "60") (name "Net-(IC41-MODE)") (class "Default")
      (node (ref "IC41") (pin "C4") (pinfunction "MODE_C4") (pintype "input"))
      (node (ref "R397") (pin "1") (pinfunction "1_1") (pintype "passive"))
      (node (ref "R399") (pin "1") (pinfunction "1_1") (pintype "passive"))
    )
    (net (code "61") (name "Net-(IC41-TRACK{slash}SS)") (class "Default")
      (node (ref "C474") (pin "1") (pinfunction "1_1") (pintype "passive"))
      (node (ref "IC41") (pin "A2") (pinfunction "TRACK/SS_A2") (pintype "input"))
    )
    (net (code "62") (name "Net-(IC42-FB)") (class "Default")
      (node (ref "IC42") (pin "5") (pinfunction "FB_5") (pintype "input"))
      (node (ref "R402") (pin "1") (pinfunction "1_1") (pintype "passive"))
      (node (ref "R406") (pin "2") (pinfunction "2_2") (pintype "passive"))
    )
    (net (code "63") (name "Net-(IC43-CT)") (class "Default")
      (node (ref "C487") (pin "2") (pinfunction "2_2") (pintype "passive"))
      (node (ref "IC43") (pin "4") (pinfunction "CT_4") (pintype "passive"))
    )
    (net (code "64") (name "Net-(IC43-SENSE)") (class "Default")
      (node (ref "IC43") (pin "5") (pinfunction "SENSE_5") (pintype "input"))
      (node (ref "R410") (pin "1") (pinfunction "1_1") (pintype "passive"))
      (node (ref "R411") (pin "2") (pinfunction "2_2") (pintype "passive"))
    )
    (net (code "65") (name "Net-(LD5-A)") (class "Default")
      (node (ref "LD5") (pin "2") (pinfunction "A_2") (pintype "passive"))
      (node (ref "R389") (pin "1") (pinfunction "1_1") (pintype "passive"))
    )
    (net (code "66") (name "Net-(T5-D)") (class "Default")
      (node (ref "R387") (pin "1") (pinfunction "1_1") (pintype "passive"))
      (node (ref "R388") (pin "2") (pinfunction "2_2") (pintype "passive"))
      (node (ref "T5") (pin "3") (pinfunction "D_3") (pintype "passive"))
    )
    (net (code "67") (name "Net-(T6-D)") (class "Default")
      (node (ref "R392") (pin "1") (pinfunction "1_1") (pintype "passive"))
      (node (ref "R393") (pin "2") (pinfunction "2_2") (pintype "passive"))
      (node (ref "T6") (pin "3") (pinfunction "D_3") (pintype "passive"))
    )
    (net (code "68") (name "Net-(T7-G)") (class "Default")
      (node (ref "C472") (pin "1") (pinfunction "1_1") (pintype "passive"))
      (node (ref "R393") (pin "1") (pinfunction "1_1") (pintype "passive"))
      (node (ref "T7") (pin "1") (pinfunction "G_1") (pintype "passive"))
    )
    (net (code "69") (name "Net-(T10A-B)") (class "Default")
      (node (ref "R400") (pin "2") (pinfunction "2_2") (pintype "passive"))
      (node (ref "R405") (pin "2") (pinfunction "2_2") (pintype "passive"))
      (node (ref "T10") (pin "2") (pinfunction "B_2") (pintype "passive"))
      (node (ref "T10") (pin "6") (pinfunction "C_6") (pintype "passive"))
    )
    (net (code "70") (name "Net-(T10B-B)") (class "Default")
      (node (ref "R400") (pin "1") (pinfunction "1_1") (pintype "passive"))
      (node (ref "T10") (pin "5") (pinfunction "B_5") (pintype "passive"))
    )
    (net (code "71") (name "Net-(T10B-C)") (class "Default")
      (node (ref "R404") (pin "2") (pinfunction "2_2") (pintype "passive"))
      (node (ref "T10") (pin "3") (pinfunction "C_3") (pintype "passive"))
      (node (ref "T8") (pin "4") (pinfunction "S_4") (pintype "passive"))
    )
    (net (code "72") (name "Net-(T11-G)") (class "Default")
      (node (ref "R408") (pin "2") (pinfunction "2_2") (pintype "passive"))
      (node (ref "T11") (pin "1") (pinfunction "G_1") (pintype "passive"))
      (node (ref "T12") (pin "3") (pinfunction "C_3") (pintype "passive"))
    )
    (net (code "73") (name "Net-(T12A-B)") (class "Default")
      (node (ref "R407") (pin "1") (pinfunction "1_1") (pintype "passive"))
      (node (ref "T12") (pin "2") (pinfunction "B_2") (pintype "passive"))
      (node (ref "T12") (pin "5") (pinfunction "B_5") (pintype "passive"))
      (node (ref "T12") (pin "6") (pinfunction "C_6") (pintype "passive"))
    )
    (net (code "74") (name "P2V5") (class "Default")
      (node (ref "C598") (pin "2") (pinfunction "2_2") (pintype "passive"))
      (node (ref "C737") (pin "2") (pinfunction "2_2") (pintype "passive"))
      (node (ref "L4") (pin "2") (pinfunction "2_2") (pintype "passive"))
      (node (ref "L5") (pin "1") (pinfunction "1_1") (pintype "passive"))
      (node (ref "R187") (pin "2") (pinfunction "2_2") (pintype "passive"))
    )
    (net (code "75") (name "P3V3MP") (class "Default")
      (node (ref "C470") (pin "2") (pinfunction "2_2") (pintype "passive"))
      (node (ref "C472") (pin "2") (pinfunction "2_2") (pintype "passive"))
      (node (ref "C488") (pin "2") (pinfunction "2_2") (pintype "passive"))
      (node (ref "IC40") (pin "4") (pinfunction "VS_4") (pintype "power_in"))
      (node (ref "IC43") (pin "3") (pinfunction "~{MR}_3") (pintype "input"))
      (node (ref "IC43") (pin "6") (pinfunction "VDD_6") (pintype "power_in"))
      (node (ref "R392") (pin "2") (pinfunction "2_2") (pintype "passive"))
      (node (ref "R401") (pin "1") (pinfunction "1_1") (pintype "passive"))
      (node (ref "R409") (pin "2") (pinfunction "2_2") (pintype "passive"))
      (node (ref "T11") (pin "2") (pinfunction "S_2") (pintype "passive"))
      (node (ref "T12") (pin "4") (pinfunction "E_4") (pintype "passive"))
      (node (ref "T7") (pin "2") (pinfunction "S_2") (pintype "passive"))
    )
    (net (code "76") (name "P3V3MP_RTM") (class "Default")
      (node (ref "F1") (pin "2") (pinfunction "2_2") (pintype "passive"))
    )
    (net (code "77") (name "P5V0") (class "Default")
      (node (ref "C477") (pin "2") (pinfunction "2_2") (pintype "passive"))
      (node (ref "C597") (pin "2") (pinfunction "2_2") (pintype "passive"))
      (node (ref "IC31") (pin "1") (pinfunction "EN_1") (pintype "input"))
      (node (ref "IC31") (pin "4") (pinfunction "VIN_4") (pintype "input"))
      (node (ref "L37") (pin "2") (pinfunction "2_2") (pintype "passive"))
    )
    (net (code "78") (name "P12V0") (class "Default")
      (node (ref "C469") (pin "2") (pinfunction "2_2") (pintype "passive"))
      (node (ref "C471") (pin "2") (pinfunction "2_2") (pintype "passive"))
      (node (ref "C478") (pin "2") (pinfunction "2_2") (pintype "passive"))
      (node (ref "C480") (pin "2") (pinfunction "2_2") (pintype "passive"))
      (node (ref "IC41") (pin "C5") (pinfunction "SVIN_C5") (pintype "power_in"))
      (node (ref "IC41") (pin "D5") (pinfunction "VIN_D5") (pintype "power_in"))
      (node (ref "IC41") (pin "E5") (pinfunction "VIN_E5") (pintype "power_in"))
      (node (ref "R387") (pin "2") (pinfunction "2_2") (pintype "passive"))
      (node (ref "R396") (pin "2") (pinfunction "2_2") (pintype "passive"))
      (node (ref "R410") (pin "2") (pinfunction "2_2") (pintype "passive"))
      (node (ref "T10") (pin "4") (pinfunction "E_4") (pintype "passive"))
      (node (ref "T4") (pin "1") (pinfunction "S_1") (pintype "passive"))
      (node (ref "T4") (pin "2") (pinfunction "S_2") (pintype "passive"))
      (node (ref "T4") (pin "3") (pinfunction "S_3") (pintype "passive"))
      (node (ref "T8") (pin "1") (pinfunction "S_1") (pintype "passive"))
      (node (ref "T8") (pin "2") (pinfunction "S_2") (pintype "passive"))
      (node (ref "T8") (pin "3") (pinfunction "S_3") (pintype "passive"))
      (node (ref "T9") (pin "5") (pinfunction "D_5") (pintype "passive"))
      (node (ref "T9") (pin "6") (pinfunction "D_6") (pintype "passive"))
      (node (ref "T9") (pin "7") (pinfunction "D_7") (pintype "passive"))
      (node (ref "T9") (pin "8") (pinfunction "D_8") (pintype "passive"))
    )
    (net (code "79") (name "P12V0_Molex") (class "Default")
      (node (ref "C479") (pin "2") (pinfunction "2_2") (pintype "passive"))
      (node (ref "D28") (pin "1") (pinfunction "C_1") (pintype "passive"))
      (node (ref "D29") (pin "2") (pinfunction "A_2") (pintype "passive"))
      (node (ref "J9") (pin "3") (pinfunction "3_3") (pintype "bidirectional"))
      (node (ref "J9") (pin "4") (pinfunction "4_4") (pintype "bidirectional"))
      (node (ref "T10") (pin "1") (pinfunction "E_1") (pintype "passive"))
      (node (ref "T8") (pin "5") (pinfunction "D_5") (pintype "passive"))
      (node (ref "T8") (pin "6") (pinfunction "D_6") (pintype "passive"))
      (node (ref "T8") (pin "7") (pinfunction "D_7") (pintype "passive"))
      (node (ref "T8") (pin "8") (pinfunction "D_8") (pintype "passive"))
    )
    (net (code "80") (name "P12V0_RTM") (class "Default")
      (node (ref "IC40") (pin "2") (pinfunction "VIN-_2") (pintype "input"))
      (node (ref "R389") (pin "2") (pinfunction "2_2") (pintype "passive"))
      (node (ref "R390") (pin "2") (pinfunction "2_2") (pintype "passive"))
    )
    (net (code "81") (name "PAYLOAD_PWR") (class "Default")
      (node (ref "C483") (pin "2") (pinfunction "2_2") (pintype "passive"))
      (node (ref "R396") (pin "1") (pinfunction "1_1") (pintype "passive"))
      (node (ref "T9") (pin "1") (pinfunction "S_1") (pintype "passive"))
      (node (ref "T9") (pin "2") (pinfunction "S_2") (pintype "passive"))
      (node (ref "T9") (pin "3") (pinfunction "S_3") (pintype "passive"))
    )
    (net (code "82") (name "unconnected-(IC41-CLKIN-PadA5)") (class "Default")
      (node (ref "IC41") (pin "A5") (pinfunction "CLKIN_A5") (pintype "input+no_connect"))
    )
    (net (code "83") (name "unconnected-(IC41-CLKOUT-PadB5)") (class "Default")
      (node (ref "IC41") (pin "B5") (pinfunction "CLKOUT_B5") (pintype "output+no_connect"))
    )
    (net (code "84") (name "unconnected-(IC41-PHMODE-PadB2)") (class "Default")
      (node (ref "IC41") (pin "B2") (pinfunction "PHMODE_B2") (pintype "input+no_connect"))
    )
    (net (code "85") (name "unconnected-(IC42-NC-Pad4)") (class "Default")
      (node (ref "IC42") (pin "4") (pinfunction "NC_4") (pintype "passive"))
    )
    (net (code "86") (name "unconnected-(IC42-PG-Pad7)") (class "Default")
      (node (ref "IC42") (pin "7") (pinfunction "PG_7") (pintype "output"))
    )
  )
)
